# EBUS2_2.net
KiCad netlist of a schematic drawn in EAGLE
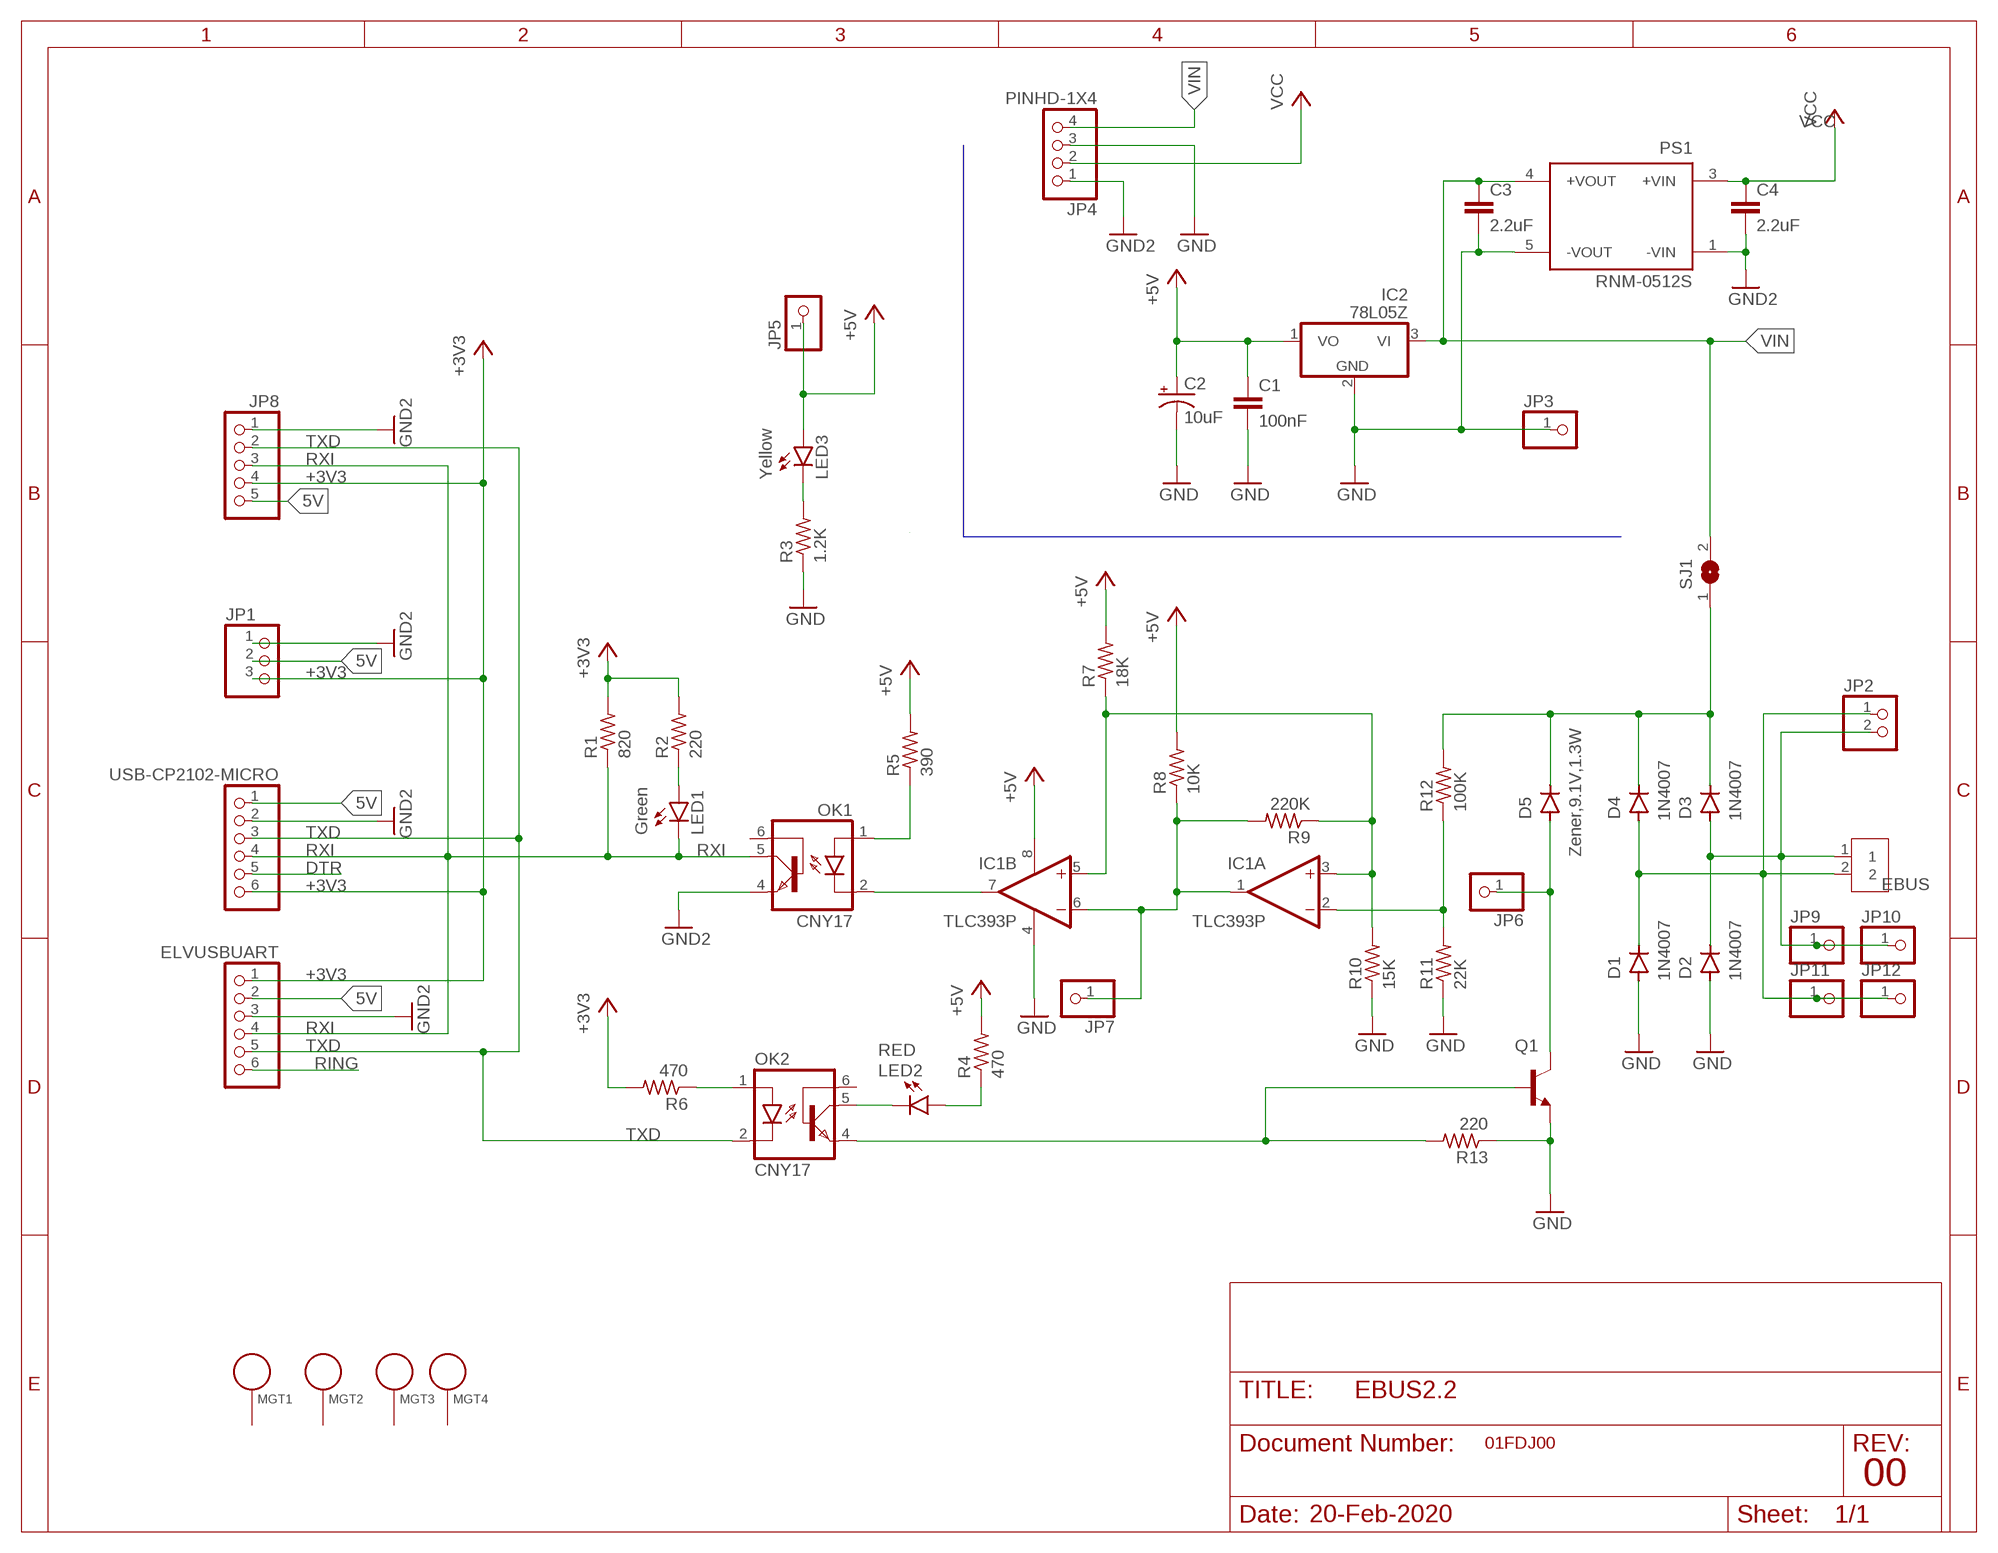
[diagram p0: schematic, sheet 1]

(export (version "E")
  (design (tool "Eeschema 10.0.6"))
  (components
    (comp (ref "C1")
      (value "100nF")
      (footprint "eagle-import:CAP-PTH-SMALL-KIT")
      (libsource (lib "eagle-import") (part "0.1UF-KIT-EZ-50V-20%"))
    )
    (comp (ref "C2")
      (value "10uF")
      (footprint "eagle-import:CPOL-RADIAL-2.5MM-5MM-KIT")
      (libsource (lib "eagle-import") (part "10UF-POLAR-RADIAL-2.5MM-KIT-25V-20%"))
    )
    (comp (ref "C3")
      (value "2.2uF")
      (footprint "eagle-import:CAP-PTH-SMALL-KIT")
      (libsource (lib "eagle-import") (part "0.1UF-KIT-EZ-50V-20%"))
    )
    (comp (ref "C4")
      (value "2.2uF")
      (footprint "eagle-import:CAP-PTH-SMALL-KIT")
      (libsource (lib "eagle-import") (part "0.1UF-KIT-EZ-50V-20%"))
    )
    (comp (ref "D1")
      (value "1N4007")
      (footprint "eagle-import:DO-41")
      (fields
        (field (name "DIGIKEY_PART_NUMBER") "1N4007MSCT-ND")
        (field (name "MANUFACTURER") "Micro Commercial Co")
        (field (name "CREATED_BY") "PCBLayout.com")
      )
      (libsource (lib "eagle-import") (part "1N4007"))
    )
    (comp (ref "D2")
      (value "1N4007")
      (footprint "eagle-import:DO-41")
      (fields
        (field (name "DIGIKEY_PART_NUMBER") "1N4007MSCT-ND")
        (field (name "MANUFACTURER") "Micro Commercial Co")
        (field (name "CREATED_BY") "PCBLayout.com")
      )
      (libsource (lib "eagle-import") (part "1N4007"))
    )
    (comp (ref "D3")
      (value "1N4007")
      (footprint "eagle-import:DO-41")
      (fields
        (field (name "DIGIKEY_PART_NUMBER") "1N4007MSCT-ND")
        (field (name "MANUFACTURER") "Micro Commercial Co")
        (field (name "CREATED_BY") "PCBLayout.com")
      )
      (libsource (lib "eagle-import") (part "1N4007"))
    )
    (comp (ref "D4")
      (value "1N4007")
      (footprint "eagle-import:DO-41")
      (fields
        (field (name "DIGIKEY_PART_NUMBER") "1N4007MSCT-ND")
        (field (name "MANUFACTURER") "Micro Commercial Co")
        (field (name "CREATED_BY") "PCBLayout.com")
      )
      (libsource (lib "eagle-import") (part "1N4007"))
    )
    (comp (ref "D5")
      (value "Zener,9.1V,1.3W")
      (footprint "eagle-import:DO-41")
      (fields
        (field (name "DIGIKEY_PART_NUMBER") "1N4007MSCT-ND")
        (field (name "MANUFACTURER") "Micro Commercial Co")
        (field (name "MPN") "1N4007")
        (field (name "CREATED_BY") "PCBLayout.com")
      )
      (libsource (lib "eagle-import") (part "1N4007"))
    )
    (comp (ref "EBUS")
      (value "2828XX-2282837-2")
      (footprint "eagle-import:TERMBLK_508-2N")
      (fields (field (name "MANUFACTURER") "TE Connectivity") (field (name "MPN") "282837-2"))
      (libsource (lib "eagle-import") (part "2828XX-2282837-2"))
    )
    (comp (ref "ELVUSBUART")
      (value "PINHD-1X6")
      (footprint "eagle-import:1X06")
      (libsource (lib "eagle-import") (part "PINHD-1X6"))
    )
    (comp (ref "IC1")
      (value "TLC393P")
      (footprint "eagle-import:DIL08")
      (libsource (lib "eagle-import") (part "TLC393P"))
    )
    (comp (ref "IC2")
      (value "78L05Z")
      (footprint "eagle-import:TO92")
      (libsource (lib "eagle-import") (part "78ZL05"))
    )
    (comp (ref "JP1")
      (value "PINHD-1X3")
      (footprint "eagle-import:1X03")
      (libsource (lib "eagle-import") (part "PINHD-1X3"))
    )
    (comp (ref "JP2")
      (value "PINHD-1X2")
      (footprint "eagle-import:1X02")
      (libsource (lib "eagle-import") (part "PINHD-1X2"))
    )
    (comp (ref "JP3")
      (value "PINHD-1X1")
      (footprint "eagle-import:1X01")
      (libsource (lib "eagle-import") (part "PINHD-1X1"))
    )
    (comp (ref "JP4")
      (value "PINHD-1X4")
      (footprint "eagle-import:1X04")
      (libsource (lib "eagle-import") (part "PINHD-1X4"))
    )
    (comp (ref "JP5")
      (value "PINHD-1X1")
      (footprint "eagle-import:1X01")
      (libsource (lib "eagle-import") (part "PINHD-1X1"))
    )
    (comp (ref "JP6")
      (value "PINHD-1X1")
      (footprint "eagle-import:1X01")
      (libsource (lib "eagle-import") (part "PINHD-1X1"))
    )
    (comp (ref "JP7")
      (value "PINHD-1X1")
      (footprint "eagle-import:1X01")
      (libsource (lib "eagle-import") (part "PINHD-1X1"))
    )
    (comp (ref "JP8")
      (value "PINHD-1X5")
      (footprint "eagle-import:1X05")
      (libsource (lib "eagle-import") (part "PINHD-1X5"))
    )
    (comp (ref "JP9")
      (value "PINHD-1X1")
      (footprint "eagle-import:1X01")
      (libsource (lib "eagle-import") (part "PINHD-1X1"))
    )
    (comp (ref "JP10")
      (value "PINHD-1X1")
      (footprint "eagle-import:1X01")
      (libsource (lib "eagle-import") (part "PINHD-1X1"))
    )
    (comp (ref "JP11")
      (value "PINHD-1X1")
      (footprint "eagle-import:1X01")
      (libsource (lib "eagle-import") (part "PINHD-1X1"))
    )
    (comp (ref "JP12")
      (value "PINHD-1X1")
      (footprint "eagle-import:1X01")
      (libsource (lib "eagle-import") (part "PINHD-1X1"))
    )
    (comp (ref "LED1")
      (value "Green")
      (footprint "eagle-import:LED5MM")
      (libsource (lib "eagle-import") (part "LED5MM"))
    )
    (comp (ref "LED2")
      (value "RED")
      (footprint "eagle-import:LED5MM")
      (libsource (lib "eagle-import") (part "LED5MM"))
    )
    (comp (ref "LED3")
      (value "Yellow")
      (footprint "eagle-import:LED5MM")
      (libsource (lib "eagle-import") (part "LED5MM"))
    )
    (comp (ref "MGT1")
      (value "MOUNTING_HOLE")
      (footprint "eagle-import:BEAGLEBONEBLACK_MOUNTING_HOLE")
      (libsource (lib "eagle-import") (part "MOUNTING_HOLE"))
    )
    (comp (ref "MGT2")
      (value "MOUNTING_HOLE")
      (footprint "eagle-import:BEAGLEBONEBLACK_MOUNTING_HOLE")
      (libsource (lib "eagle-import") (part "MOUNTING_HOLE"))
    )
    (comp (ref "MGT3")
      (value "MOUNTING_HOLE")
      (footprint "eagle-import:BEAGLEBONEBLACK_MOUNTING_HOLE")
      (libsource (lib "eagle-import") (part "MOUNTING_HOLE"))
    )
    (comp (ref "MGT4")
      (value "MOUNTING_HOLE")
      (footprint "eagle-import:BEAGLEBONEBLACK_MOUNTING_HOLE")
      (libsource (lib "eagle-import") (part "MOUNTING_HOLE"))
    )
    (comp (ref "OK1")
      (value "CNY17")
      (footprint "eagle-import:DIL06")
      (fields (field (name "MPN") "CNY17-1"))
      (libsource (lib "eagle-import") (part "CNY17"))
    )
    (comp (ref "OK2")
      (value "CNY17")
      (footprint "eagle-import:DIL06")
      (fields (field (name "MPN") "CNY17-1"))
      (libsource (lib "eagle-import") (part "CNY17"))
    )
    (comp (ref "PS1")
      (value "RNM-0512S")
      (footprint "eagle-import:CONV_RNM-0512S")
      (fields (field (name "MF") "Recom Power"))
      (libsource (lib "eagle-import") (part "RNM-0512S"))
    )
    (comp (ref "Q1")
      (value "BC337-NPN-TO92-CBE")
      (footprint "eagle-import:TO92-CBE")
      (libsource (lib "eagle-import") (part "-NPN-TO92-CBEBC337"))
    )
    (comp (ref "R1")
      (value "820")
      (footprint "eagle-import:0204_7")
      (libsource (lib "eagle-import") (part "R-US_0204/7"))
    )
    (comp (ref "R2")
      (value "220")
      (footprint "eagle-import:0204_7")
      (libsource (lib "eagle-import") (part "R-US_0204/7"))
    )
    (comp (ref "R3")
      (value "1.2K")
      (footprint "eagle-import:0204_7")
      (libsource (lib "eagle-import") (part "R-US_0204/7"))
    )
    (comp (ref "R4")
      (value "470")
      (footprint "eagle-import:0204_7")
      (libsource (lib "eagle-import") (part "R-US_0204/7"))
    )
    (comp (ref "R5")
      (value "390")
      (footprint "eagle-import:0204_7")
      (libsource (lib "eagle-import") (part "R-US_0204/7"))
    )
    (comp (ref "R6")
      (value "470")
      (footprint "eagle-import:0204_7")
      (libsource (lib "eagle-import") (part "R-US_0204/7"))
    )
    (comp (ref "R7")
      (value "18K")
      (footprint "eagle-import:0204_7")
      (libsource (lib "eagle-import") (part "R-US_0204/7"))
    )
    (comp (ref "R8")
      (value "10K")
      (footprint "eagle-import:0204_7")
      (libsource (lib "eagle-import") (part "R-US_0204/7"))
    )
    (comp (ref "R9")
      (value "220K")
      (footprint "eagle-import:0204_7")
      (libsource (lib "eagle-import") (part "R-US_0204/7"))
    )
    (comp (ref "R10")
      (value "15K")
      (footprint "eagle-import:0204_7")
      (libsource (lib "eagle-import") (part "R-US_0204/7"))
    )
    (comp (ref "R11")
      (value "22K")
      (footprint "eagle-import:0204_7")
      (libsource (lib "eagle-import") (part "R-US_0204/7"))
    )
    (comp (ref "R12")
      (value "100K")
      (footprint "eagle-import:0204_7")
      (libsource (lib "eagle-import") (part "R-US_0204/7"))
    )
    (comp (ref "R13")
      (value "220")
      (footprint "eagle-import:0204_7")
      (libsource (lib "eagle-import") (part "R-US_0204/7"))
    )
    (comp (ref "SJ1")
      (value "SJW")
      (footprint "eagle-import:SJW")
      (libsource (lib "eagle-import") (part "SJW"))
    )
    (comp (ref "USB-CP2102-MICRO")
      (value "PINHD-1X6")
      (footprint "eagle-import:1X06")
      (libsource (lib "eagle-import") (part "PINHD-1X6"))
    )
  )
  (nets
    (net (code "1") (name "+3V3") (class "Default")
      (node (ref "ELVUSBUART") (pin "1") (pinfunction "1_1") (pintype "passive"))
      (node (ref "JP1") (pin "3") (pinfunction "3_3") (pintype "passive"))
      (node (ref "JP8") (pin "4") (pinfunction "4_4") (pintype "passive"))
      (node (ref "R1") (pin "2") (pinfunction "2_2") (pintype "passive"))
      (node (ref "R2") (pin "2") (pinfunction "2_2") (pintype "passive"))
      (node (ref "R6") (pin "2") (pinfunction "2_2") (pintype "passive"))
      (node (ref "USB-CP2102-MICRO") (pin "6") (pinfunction "6_6") (pintype "passive"))
    )
    (net (code "2") (name "+5V") (class "Default")
      (node (ref "C1") (pin "1") (pinfunction "1_1") (pintype "passive"))
      (node (ref "C2") (pin "1") (pinfunction "+_1") (pintype "passive"))
      (node (ref "IC1") (pin "8") (pinfunction "V+_8") (pintype "power_in"))
      (node (ref "IC2") (pin "1") (pinfunction "VO_1") (pintype "passive"))
      (node (ref "JP5") (pin "1") (pinfunction "1_1") (pintype "passive"))
      (node (ref "LED3") (pin "A") (pinfunction "A_A") (pintype "passive"))
      (node (ref "R4") (pin "2") (pinfunction "2_2") (pintype "passive"))
      (node (ref "R5") (pin "2") (pinfunction "2_2") (pintype "passive"))
      (node (ref "R7") (pin "2") (pinfunction "2_2") (pintype "passive"))
      (node (ref "R8") (pin "2") (pinfunction "2_2") (pintype "passive"))
    )
    (net (code "3") (name "/DTR") (class "Default")
      (node (ref "USB-CP2102-MICRO") (pin "5") (pinfunction "5_5") (pintype "passive"))
    )
    (net (code "4") (name "/RING") (class "Default")
      (node (ref "ELVUSBUART") (pin "6") (pinfunction "6_6") (pintype "passive"))
    )
    (net (code "5") (name "/RXI") (class "Default")
      (node (ref "ELVUSBUART") (pin "4") (pinfunction "4_4") (pintype "passive"))
      (node (ref "JP8") (pin "3") (pinfunction "3_3") (pintype "passive"))
      (node (ref "LED1") (pin "K") (pinfunction "C_K") (pintype "passive"))
      (node (ref "OK1") (pin "5") (pinfunction "COL_5") (pintype "passive"))
      (node (ref "R1") (pin "1") (pinfunction "1_1") (pintype "passive"))
      (node (ref "USB-CP2102-MICRO") (pin "4") (pinfunction "4_4") (pintype "passive"))
    )
    (net (code "6") (name "/TXD") (class "Default")
      (node (ref "ELVUSBUART") (pin "5") (pinfunction "5_5") (pintype "passive"))
      (node (ref "JP8") (pin "2") (pinfunction "2_2") (pintype "passive"))
      (node (ref "OK2") (pin "2") (pinfunction "C_2") (pintype "passive"))
      (node (ref "USB-CP2102-MICRO") (pin "3") (pinfunction "3_3") (pintype "passive"))
    )
    (net (code "7") (name "5V") (class "Default")
      (node (ref "ELVUSBUART") (pin "2") (pinfunction "2_2") (pintype "passive"))
      (node (ref "JP1") (pin "2") (pinfunction "2_2") (pintype "passive"))
      (node (ref "JP8") (pin "5") (pinfunction "5_5") (pintype "passive"))
      (node (ref "USB-CP2102-MICRO") (pin "1") (pinfunction "1_1") (pintype "passive"))
    )
    (net (code "8") (name "GND") (class "Default")
      (node (ref "C1") (pin "2") (pinfunction "2_2") (pintype "passive"))
      (node (ref "C2") (pin "2") (pinfunction "-_2") (pintype "passive"))
      (node (ref "C3") (pin "2") (pinfunction "2_2") (pintype "passive"))
      (node (ref "C4") (pin "2") (pinfunction "2_2") (pintype "passive"))
      (node (ref "D1") (pin "A") (pinfunction "A_A") (pintype "passive"))
      (node (ref "D2") (pin "A") (pinfunction "A_A") (pintype "passive"))
      (node (ref "ELVUSBUART") (pin "3") (pinfunction "3_3") (pintype "passive"))
      (node (ref "IC1") (pin "4") (pinfunction "V-_4") (pintype "power_in"))
      (node (ref "IC2") (pin "2") (pinfunction "GND_2") (pintype "passive"))
      (node (ref "JP1") (pin "1") (pinfunction "1_1") (pintype "passive"))
      (node (ref "JP3") (pin "1") (pinfunction "1_1") (pintype "passive"))
      (node (ref "JP4") (pin "1") (pinfunction "1_1") (pintype "passive"))
      (node (ref "JP4") (pin "3") (pinfunction "3_3") (pintype "passive"))
      (node (ref "JP8") (pin "1") (pinfunction "1_1") (pintype "passive"))
      (node (ref "OK1") (pin "4") (pinfunction "EMI_4") (pintype "passive"))
      (node (ref "PS1") (pin "1") (pinfunction "-VIN_1") (pintype "input"))
      (node (ref "PS1") (pin "5") (pinfunction "-VOUT_5") (pintype "output"))
      (node (ref "Q1") (pin "E") (pinfunction "E_E") (pintype "passive"))
      (node (ref "R10") (pin "1") (pinfunction "1_1") (pintype "passive"))
      (node (ref "R11") (pin "1") (pinfunction "1_1") (pintype "passive"))
      (node (ref "R13") (pin "1") (pinfunction "1_1") (pintype "passive"))
      (node (ref "R3") (pin "1") (pinfunction "1_1") (pintype "passive"))
      (node (ref "USB-CP2102-MICRO") (pin "2") (pinfunction "2_2") (pintype "passive"))
    )
    (net (code "9") (name "Net-(D1-PadC)") (class "Default")
      (node (ref "D1") (pin "C") (pinfunction "C_C") (pintype "passive"))
      (node (ref "D4") (pin "A") (pinfunction "A_A") (pintype "passive"))
      (node (ref "EBUS") (pin "2") (pinfunction "2_2") (pintype "bidirectional"))
      (node (ref "JP11") (pin "1") (pinfunction "1_1") (pintype "passive"))
      (node (ref "JP12") (pin "1") (pinfunction "1_1") (pintype "passive"))
      (node (ref "JP2") (pin "1") (pinfunction "1_1") (pintype "passive"))
    )
    (net (code "10") (name "Net-(D2-PadC)") (class "Default")
      (node (ref "D2") (pin "C") (pinfunction "C_C") (pintype "passive"))
      (node (ref "D3") (pin "A") (pinfunction "A_A") (pintype "passive"))
      (node (ref "EBUS") (pin "1") (pinfunction "1_1") (pintype "bidirectional"))
      (node (ref "JP10") (pin "1") (pinfunction "1_1") (pintype "passive"))
      (node (ref "JP2") (pin "2") (pinfunction "2_2") (pintype "passive"))
      (node (ref "JP9") (pin "1") (pinfunction "1_1") (pintype "passive"))
    )
    (net (code "11") (name "Net-(D3-PadC)") (class "Default")
      (node (ref "D3") (pin "C") (pinfunction "C_C") (pintype "passive"))
      (node (ref "D4") (pin "C") (pinfunction "C_C") (pintype "passive"))
      (node (ref "D5") (pin "C") (pinfunction "C_C") (pintype "passive"))
      (node (ref "R12") (pin "2") (pinfunction "2_2") (pintype "passive"))
      (node (ref "SJ1") (pin "1") (pinfunction "1_1") (pintype "passive"))
    )
    (net (code "12") (name "Net-(D5-PadA)") (class "Default")
      (node (ref "D5") (pin "A") (pinfunction "A_A") (pintype "passive"))
      (node (ref "JP6") (pin "1") (pinfunction "1_1") (pintype "passive"))
      (node (ref "Q1") (pin "C") (pinfunction "C_C") (pintype "passive"))
    )
    (net (code "13") (name "Net-(IC1A-+IN)") (class "Default")
      (node (ref "IC1") (pin "3") (pinfunction "+IN_3") (pintype "input"))
      (node (ref "IC1") (pin "5") (pinfunction "+IN_5") (pintype "input"))
      (node (ref "R10") (pin "2") (pinfunction "2_2") (pintype "passive"))
      (node (ref "R7") (pin "1") (pinfunction "1_1") (pintype "passive"))
      (node (ref "R9") (pin "1") (pinfunction "1_1") (pintype "passive"))
    )
    (net (code "14") (name "Net-(IC1A--IN)") (class "Default")
      (node (ref "IC1") (pin "2") (pinfunction "-IN_2") (pintype "input"))
      (node (ref "R11") (pin "2") (pinfunction "2_2") (pintype "passive"))
      (node (ref "R12") (pin "1") (pinfunction "1_1") (pintype "passive"))
    )
    (net (code "15") (name "Net-(IC1A-OUT)") (class "Default")
      (node (ref "IC1") (pin "1") (pinfunction "OUT_1") (pintype "output"))
      (node (ref "IC1") (pin "6") (pinfunction "-IN_6") (pintype "input"))
      (node (ref "JP7") (pin "1") (pinfunction "1_1") (pintype "passive"))
      (node (ref "R8") (pin "1") (pinfunction "1_1") (pintype "passive"))
      (node (ref "R9") (pin "2") (pinfunction "2_2") (pintype "passive"))
    )
    (net (code "16") (name "Net-(IC1B-OUT)") (class "Default")
      (node (ref "IC1") (pin "7") (pinfunction "OUT_7") (pintype "output"))
      (node (ref "OK1") (pin "2") (pinfunction "C_2") (pintype "passive"))
    )
    (net (code "17") (name "Net-(LED1-PadA)") (class "Default")
      (node (ref "LED1") (pin "A") (pinfunction "A_A") (pintype "passive"))
      (node (ref "R2") (pin "1") (pinfunction "1_1") (pintype "passive"))
    )
    (net (code "18") (name "Net-(LED2-C)") (class "Default")
      (node (ref "LED2") (pin "K") (pinfunction "C_K") (pintype "passive"))
      (node (ref "OK2") (pin "5") (pinfunction "COL_5") (pintype "passive"))
    )
    (net (code "19") (name "Net-(LED2-PadA)") (class "Default")
      (node (ref "LED2") (pin "A") (pinfunction "A_A") (pintype "passive"))
      (node (ref "R4") (pin "1") (pinfunction "1_1") (pintype "passive"))
    )
    (net (code "20") (name "Net-(LED3-C)") (class "Default")
      (node (ref "LED3") (pin "K") (pinfunction "C_K") (pintype "passive"))
      (node (ref "R3") (pin "2") (pinfunction "2_2") (pintype "passive"))
    )
    (net (code "21") (name "Net-(OK1-A)") (class "Default")
      (node (ref "OK1") (pin "1") (pinfunction "A_1") (pintype "passive"))
      (node (ref "R5") (pin "1") (pinfunction "1_1") (pintype "passive"))
    )
    (net (code "22") (name "Net-(OK2-A)") (class "Default")
      (node (ref "OK2") (pin "1") (pinfunction "A_1") (pintype "passive"))
      (node (ref "R6") (pin "1") (pinfunction "1_1") (pintype "passive"))
    )
    (net (code "23") (name "Net-(OK2-EMI)") (class "Default")
      (node (ref "OK2") (pin "4") (pinfunction "EMI_4") (pintype "passive"))
      (node (ref "Q1") (pin "B") (pinfunction "B_B") (pintype "passive"))
      (node (ref "R13") (pin "2") (pinfunction "2_2") (pintype "passive"))
    )
    (net (code "24") (name "VCC") (class "Default")
      (node (ref "C4") (pin "1") (pinfunction "1_1") (pintype "passive"))
      (node (ref "JP4") (pin "2") (pinfunction "2_2") (pintype "passive"))
      (node (ref "PS1") (pin "3") (pinfunction "+VIN_3") (pintype "input"))
    )
    (net (code "25") (name "VIN") (class "Default")
      (node (ref "C3") (pin "1") (pinfunction "1_1") (pintype "passive"))
      (node (ref "IC2") (pin "3") (pinfunction "VI_3") (pintype "input"))
      (node (ref "JP4") (pin "4") (pinfunction "4_4") (pintype "passive"))
      (node (ref "PS1") (pin "4") (pinfunction "+VOUT_4") (pintype "output"))
      (node (ref "SJ1") (pin "2") (pinfunction "2_2") (pintype "passive"))
    )
    (net (code "26") (name "unconnected-(MGT1-PadP$1)") (class "Default")
      (node (ref "MGT1") (pin "P$1") (pinfunction "P$1_P$1") (pintype "bidirectional"))
    )
    (net (code "27") (name "unconnected-(MGT2-PadP$1)") (class "Default")
      (node (ref "MGT2") (pin "P$1") (pinfunction "P$1_P$1") (pintype "bidirectional"))
    )
    (net (code "28") (name "unconnected-(MGT3-PadP$1)") (class "Default")
      (node (ref "MGT3") (pin "P$1") (pinfunction "P$1_P$1") (pintype "bidirectional"))
    )
    (net (code "29") (name "unconnected-(MGT4-PadP$1)") (class "Default")
      (node (ref "MGT4") (pin "P$1") (pinfunction "P$1_P$1") (pintype "bidirectional"))
    )
    (net (code "30") (name "unconnected-(OK1-BAS-Pad6)") (class "Default")
      (node (ref "OK1") (pin "6") (pinfunction "BAS_6") (pintype "passive"))
    )
    (net (code "31") (name "unconnected-(OK2-BAS-Pad6)") (class "Default")
      (node (ref "OK2") (pin "6") (pinfunction "BAS_6") (pintype "passive"))
    )
  )
)
